# arm-pro-nada.net
KiCad netlist of a schematic drawn in EAGLE
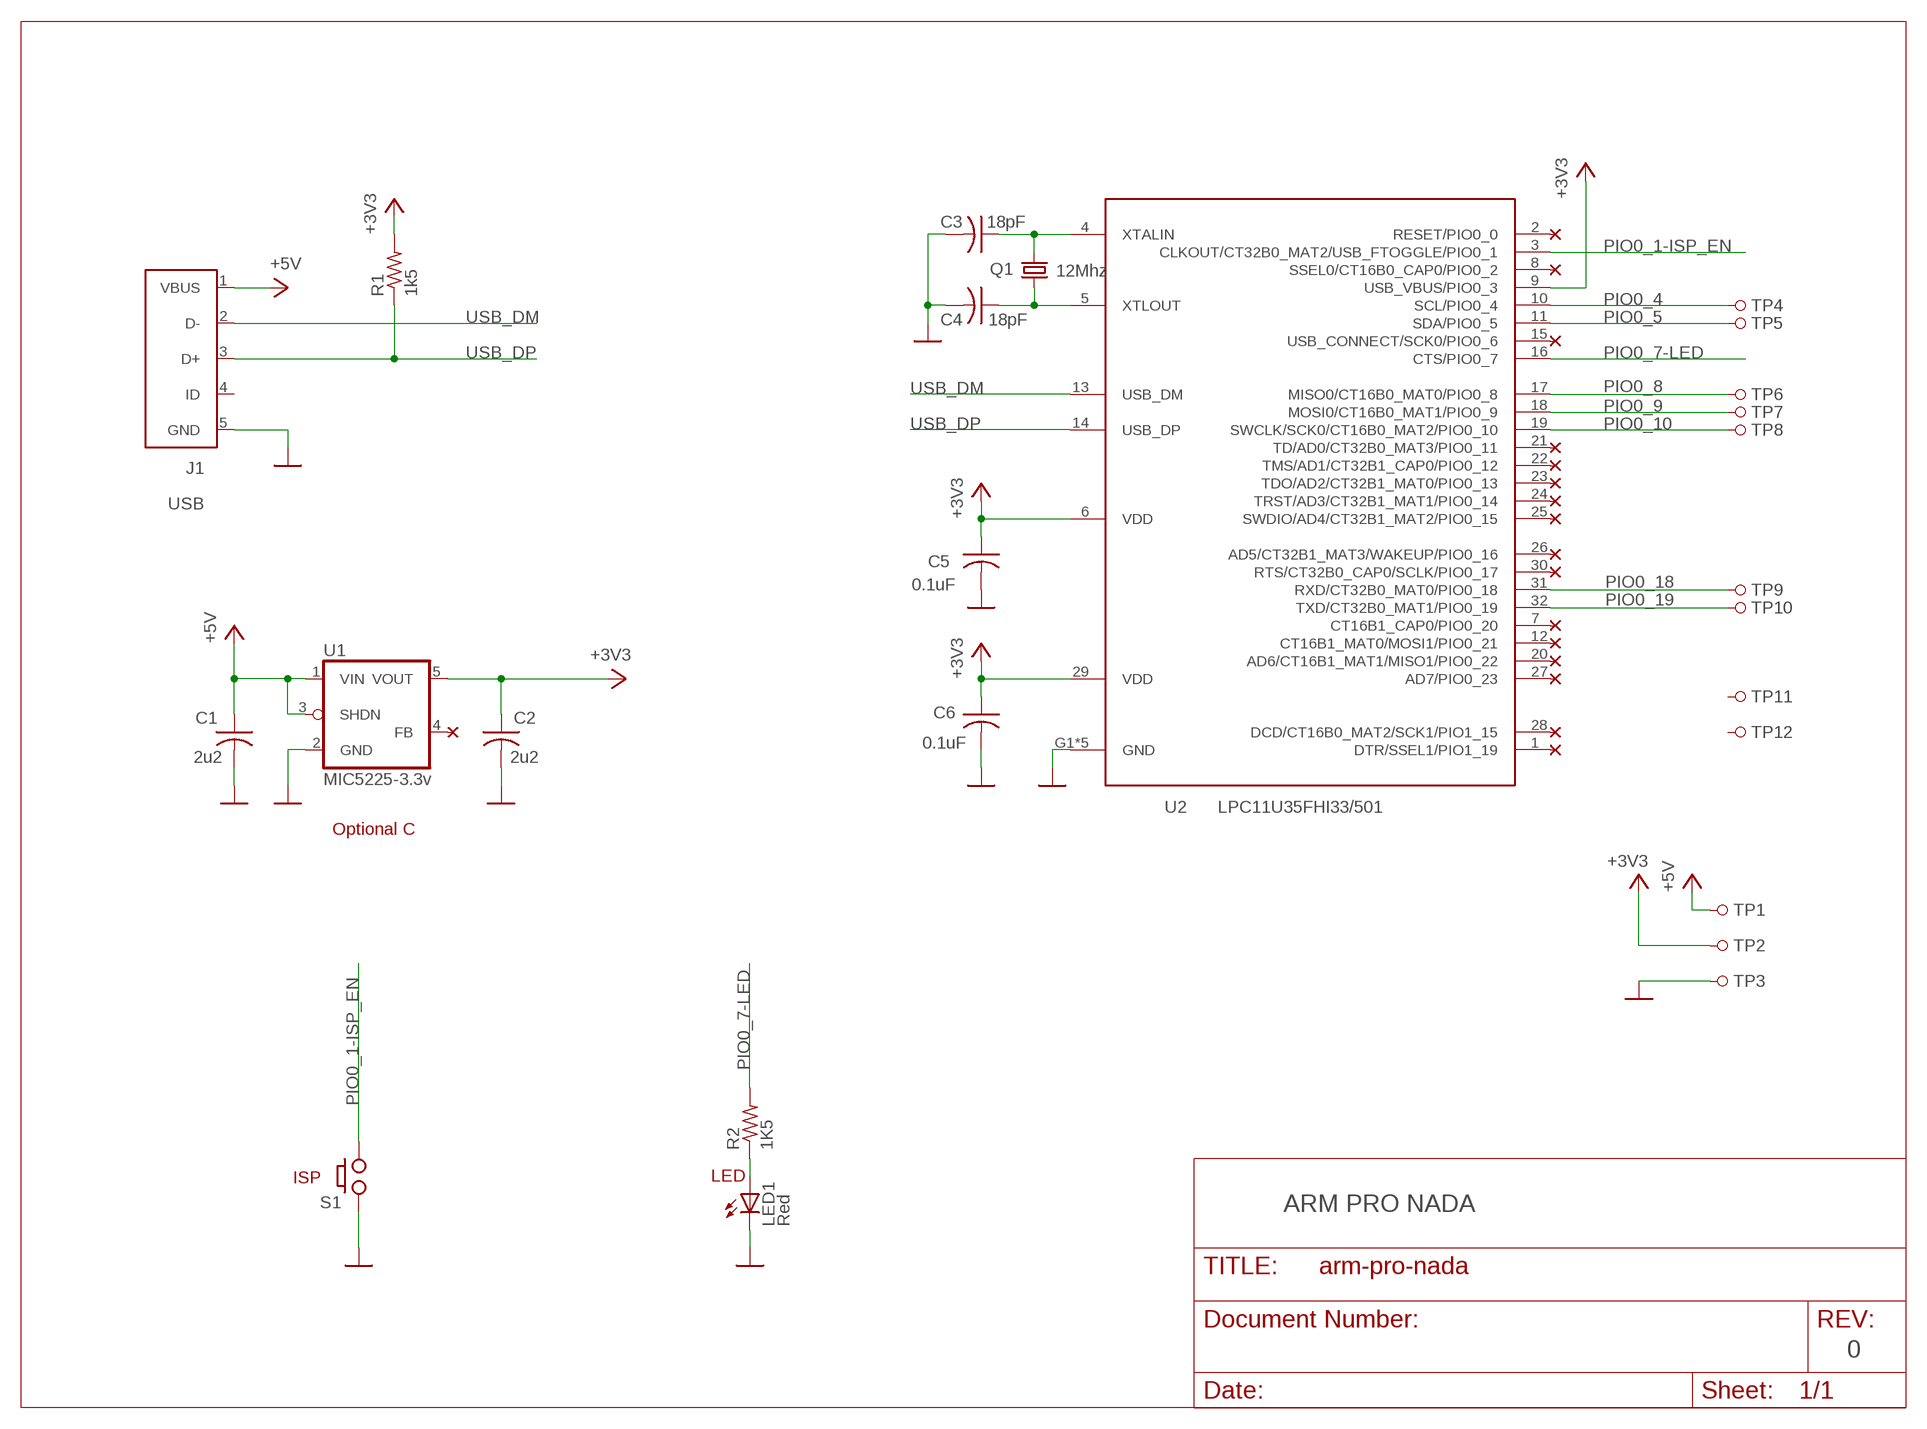
[diagram p0: schematic, sheet 1]

(export (version "E")
  (design (tool "Eeschema 10.0.6"))
  (components
    (comp (ref "C1")
      (value "2u2")
      (footprint "eagle-import:C0402K")
      (libsource (lib "eagle-import") (part "C-USC0402K"))
    )
    (comp (ref "C2")
      (value "2u2")
      (footprint "eagle-import:C0402K")
      (libsource (lib "eagle-import") (part "C-USC0402K"))
    )
    (comp (ref "C3")
      (value "18pF")
      (footprint "eagle-import:C0402K")
      (libsource (lib "eagle-import") (part "C-USC0402K"))
    )
    (comp (ref "C4")
      (value "18pF")
      (footprint "eagle-import:C0402K")
      (libsource (lib "eagle-import") (part "C-USC0402K"))
    )
    (comp (ref "C5")
      (value "0.1uF")
      (footprint "eagle-import:C0402K")
      (libsource (lib "eagle-import") (part "C-USC0402K"))
    )
    (comp (ref "C6")
      (value "0.1uF")
      (footprint "eagle-import:C0402K")
      (libsource (lib "eagle-import") (part "C-USC0402K"))
    )
    (comp (ref "J1")
      (value "USB")
      (footprint "eagle-import:USB-MICRO-ZX62RD-AB-5P8")
      (libsource (lib "eagle-import") (part "USB"))
    )
    (comp (ref "LED1")
      (value "Red")
      (footprint "eagle-import:CHIP-LED0603")
      (libsource (lib "eagle-import") (part "LEDCHIP-LED0603"))
    )
    (comp (ref "Q1")
      (value "12Mhz")
      (footprint "eagle-import:CRYSTAL")
      (libsource (lib "eagle-import") (part "CRYSTALCTS406"))
    )
    (comp (ref "R1")
      (value "1k5")
      (footprint "eagle-import:R0402")
      (libsource (lib "eagle-import") (part "R-US_R0402"))
    )
    (comp (ref "R2")
      (value "1K5")
      (footprint "eagle-import:R0402")
      (libsource (lib "eagle-import") (part "R-US_R0402"))
    )
    (comp (ref "S1")
      (value "PUSH_BUTTON")
      (footprint "eagle-import:PUSH_BUTTON")
      (libsource (lib "eagle-import") (part "PUSH_BUTTON"))
    )
    (comp (ref "TP1")
      (value "HDR1")
      (footprint "eagle-import:1X01")
      (libsource (lib "eagle-import") (part "PINHD-1X1"))
    )
    (comp (ref "TP2")
      (value "HDR1")
      (footprint "eagle-import:1X01")
      (libsource (lib "eagle-import") (part "PINHD-1X1"))
    )
    (comp (ref "TP3")
      (value "HDR1")
      (footprint "eagle-import:1X01")
      (libsource (lib "eagle-import") (part "PINHD-1X1"))
    )
    (comp (ref "TP4")
      (value "HDR1")
      (footprint "eagle-import:1X01")
      (libsource (lib "eagle-import") (part "PINHD-1X1"))
    )
    (comp (ref "TP5")
      (value "HDR1")
      (footprint "eagle-import:1X01")
      (libsource (lib "eagle-import") (part "PINHD-1X1"))
    )
    (comp (ref "TP6")
      (value "HDR1")
      (footprint "eagle-import:1X01")
      (libsource (lib "eagle-import") (part "PINHD-1X1"))
    )
    (comp (ref "TP7")
      (value "HDR1")
      (footprint "eagle-import:1X01")
      (libsource (lib "eagle-import") (part "PINHD-1X1"))
    )
    (comp (ref "TP8")
      (value "HDR1")
      (footprint "eagle-import:1X01")
      (libsource (lib "eagle-import") (part "PINHD-1X1"))
    )
    (comp (ref "TP9")
      (value "HDR1")
      (footprint "eagle-import:1X01")
      (libsource (lib "eagle-import") (part "PINHD-1X1"))
    )
    (comp (ref "TP10")
      (value "HDR1")
      (footprint "eagle-import:1X01")
      (libsource (lib "eagle-import") (part "PINHD-1X1"))
    )
    (comp (ref "TP11")
      (value "HDR1")
      (footprint "eagle-import:1X01")
      (libsource (lib "eagle-import") (part "PINHD-1X1"))
    )
    (comp (ref "TP12")
      (value "HDR1")
      (footprint "eagle-import:1X01")
      (libsource (lib "eagle-import") (part "PINHD-1X1"))
    )
    (comp (ref "U1")
      (value "MIC5225-3.3v")
      (footprint "eagle-import:SOT25")
      (libsource (lib "eagle-import") (part "TC1015"))
    )
    (comp (ref "U2")
      (value "LPC11U35FHI33/501")
      (footprint "eagle-import:HVQFN33-5MM")
      (libsource (lib "eagle-import") (part "LPC11U35FHN33/501"))
    )
  )
  (nets
    (net (code "1") (name "+3V3") (class "Default")
      (node (ref "C2") (pin "1") (pinfunction "1_1") (pintype "passive"))
      (node (ref "C5") (pin "1") (pinfunction "1_1") (pintype "passive"))
      (node (ref "C6") (pin "1") (pinfunction "1_1") (pintype "passive"))
      (node (ref "R1") (pin "2") (pinfunction "2_2") (pintype "passive"))
      (node (ref "TP2") (pin "1") (pinfunction "1_1") (pintype "passive"))
      (node (ref "U1") (pin "5") (pinfunction "VOUT_5") (pintype "power_in"))
      (node (ref "U2") (pin "29") (pinfunction "VDD_29") (pintype "bidirectional"))
      (node (ref "U2") (pin "6") (pinfunction "VDD_6") (pintype "bidirectional"))
      (node (ref "U2") (pin "9") (pinfunction "USB_VBUS/PIO0_3_9") (pintype "bidirectional"))
    )
    (net (code "2") (name "+5V") (class "Default")
      (node (ref "C1") (pin "1") (pinfunction "1_1") (pintype "passive"))
      (node (ref "J1") (pin "1") (pinfunction "VBUS_1") (pintype "bidirectional"))
      (node (ref "TP1") (pin "1") (pinfunction "1_1") (pintype "passive"))
      (node (ref "U1") (pin "1") (pinfunction "VIN_1") (pintype "power_in"))
      (node (ref "U1") (pin "3") (pinfunction "SHDN_3") (pintype "input"))
    )
    (net (code "3") (name "/PIO0_1-ISP_EN") (class "Default")
      (node (ref "S1") (pin "B2") (pinfunction "2_B2") (pintype "passive"))
      (node (ref "U2") (pin "3") (pinfunction "CLKOUT/CT32B0_MAT2/USB_FTOGGLE/PIO0_1_3") (pintype "bidirectional"))
    )
    (net (code "4") (name "/PIO0_4") (class "Default")
      (node (ref "TP4") (pin "1") (pinfunction "1_1") (pintype "passive"))
      (node (ref "U2") (pin "10") (pinfunction "SCL/PIO0_4_10") (pintype "bidirectional"))
    )
    (net (code "5") (name "/PIO0_5") (class "Default")
      (node (ref "TP5") (pin "1") (pinfunction "1_1") (pintype "passive"))
      (node (ref "U2") (pin "11") (pinfunction "SDA/PIO0_5_11") (pintype "bidirectional"))
    )
    (net (code "6") (name "/PIO0_7-LED") (class "Default")
      (node (ref "R2") (pin "2") (pinfunction "2_2") (pintype "passive"))
      (node (ref "U2") (pin "16") (pinfunction "CTS/PIO0_7_16") (pintype "bidirectional"))
    )
    (net (code "7") (name "/PIO0_8") (class "Default")
      (node (ref "TP6") (pin "1") (pinfunction "1_1") (pintype "passive"))
      (node (ref "U2") (pin "17") (pinfunction "MISO0/CT16B0_MAT0/PIO0_8_17") (pintype "bidirectional"))
    )
    (net (code "8") (name "/PIO0_9") (class "Default")
      (node (ref "TP7") (pin "1") (pinfunction "1_1") (pintype "passive"))
      (node (ref "U2") (pin "18") (pinfunction "MOSI0/CT16B0_MAT1/PIO0_9_18") (pintype "bidirectional"))
    )
    (net (code "9") (name "/PIO0_10") (class "Default")
      (node (ref "TP8") (pin "1") (pinfunction "1_1") (pintype "passive"))
      (node (ref "U2") (pin "19") (pinfunction "SWCLK/SCK0/CT16B0_MAT2/PIO0_10_19") (pintype "bidirectional"))
    )
    (net (code "10") (name "/PIO0_18") (class "Default")
      (node (ref "TP9") (pin "1") (pinfunction "1_1") (pintype "passive"))
      (node (ref "U2") (pin "31") (pinfunction "RXD/CT32B0_MAT0/PIO0_18_31") (pintype "bidirectional"))
    )
    (net (code "11") (name "/PIO0_19") (class "Default")
      (node (ref "TP10") (pin "1") (pinfunction "1_1") (pintype "passive"))
      (node (ref "U2") (pin "32") (pinfunction "TXD/CT32B0_MAT1/PIO0_19_32") (pintype "bidirectional"))
    )
    (net (code "12") (name "/USB_DM") (class "Default")
      (node (ref "J1") (pin "2") (pinfunction "D-_2") (pintype "bidirectional"))
      (node (ref "U2") (pin "13") (pinfunction "USB_DM_13") (pintype "bidirectional"))
    )
    (net (code "13") (name "/USB_DP") (class "Default")
      (node (ref "J1") (pin "3") (pinfunction "D+_3") (pintype "bidirectional"))
      (node (ref "R1") (pin "1") (pinfunction "1_1") (pintype "passive"))
      (node (ref "U2") (pin "14") (pinfunction "USB_DP_14") (pintype "bidirectional"))
    )
    (net (code "14") (name "GND") (class "Default")
      (node (ref "C1") (pin "2") (pinfunction "2_2") (pintype "passive"))
      (node (ref "C2") (pin "2") (pinfunction "2_2") (pintype "passive"))
      (node (ref "C3") (pin "2") (pinfunction "2_2") (pintype "passive"))
      (node (ref "C4") (pin "2") (pinfunction "2_2") (pintype "passive"))
      (node (ref "C5") (pin "2") (pinfunction "2_2") (pintype "passive"))
      (node (ref "C6") (pin "2") (pinfunction "2_2") (pintype "passive"))
      (node (ref "J1") (pin "5") (pinfunction "GND_5") (pintype "bidirectional"))
      (node (ref "LED1") (pin "C") (pinfunction "C_C") (pintype "passive"))
      (node (ref "S1") (pin "A1") (pinfunction "1_A1") (pintype "passive"))
      (node (ref "TP3") (pin "1") (pinfunction "1_1") (pintype "passive"))
      (node (ref "U1") (pin "2") (pinfunction "GND_2") (pintype "power_in"))
      (node (ref "U2") (pin "G1") (pinfunction "GND_G1") (pintype "bidirectional"))
      (node (ref "U2") (pin "G2") (pinfunction "GND_G2") (pintype "bidirectional"))
      (node (ref "U2") (pin "G3") (pinfunction "GND_G3") (pintype "bidirectional"))
      (node (ref "U2") (pin "G4") (pinfunction "GND_G4") (pintype "bidirectional"))
      (node (ref "U2") (pin "TAB") (pinfunction "GND_TAB") (pintype "bidirectional"))
    )
    (net (code "15") (name "Net-(LED1-PadA)") (class "Default")
      (node (ref "LED1") (pin "A") (pinfunction "A_A") (pintype "passive"))
      (node (ref "R2") (pin "1") (pinfunction "1_1") (pintype "passive"))
    )
    (net (code "16") (name "Net-(Q1-2)") (class "Default")
      (node (ref "C3") (pin "1") (pinfunction "1_1") (pintype "passive"))
      (node (ref "Q1") (pin "3") (pinfunction "2_3") (pintype "passive"))
      (node (ref "U2") (pin "4") (pinfunction "XTALIN_4") (pintype "bidirectional"))
    )
    (net (code "17") (name "Net-(U2-XTLOUT)") (class "Default")
      (node (ref "C4") (pin "1") (pinfunction "1_1") (pintype "passive"))
      (node (ref "Q1") (pin "1") (pinfunction "1_1") (pintype "passive"))
      (node (ref "U2") (pin "5") (pinfunction "XTLOUT_5") (pintype "bidirectional"))
    )
    (net (code "18") (name "unconnected-(J1-ID-Pad4)") (class "Default")
      (node (ref "J1") (pin "4") (pinfunction "ID_4") (pintype "bidirectional"))
    )
    (net (code "19") (name "unconnected-(TP11-Pad1)") (class "Default")
      (node (ref "TP11") (pin "1") (pinfunction "1_1") (pintype "passive"))
    )
    (net (code "20") (name "unconnected-(TP12-Pad1)") (class "Default")
      (node (ref "TP12") (pin "1") (pinfunction "1_1") (pintype "passive"))
    )
    (net (code "21") (name "unconnected-(U1-FB-Pad4)") (class "Default")
      (node (ref "U1") (pin "4") (pinfunction "FB_4") (pintype "passive"))
    )
    (net (code "22") (name "unconnected-(U2-AD5{slash}CT32B1_MAT3{slash}WAKEUP{slash}PIO0_16-Pad26)") (class "Default")
      (node (ref "U2") (pin "26") (pinfunction "AD5/CT32B1_MAT3/WAKEUP/PIO0_16_26") (pintype "bidirectional"))
    )
    (net (code "23") (name "unconnected-(U2-AD6{slash}CT16B1_MAT1{slash}MISO1{slash}PIO0_22-Pad20)") (class "Default")
      (node (ref "U2") (pin "20") (pinfunction "AD6/CT16B1_MAT1/MISO1/PIO0_22_20") (pintype "bidirectional"))
    )
    (net (code "24") (name "unconnected-(U2-AD7{slash}PIO0_23-Pad27)") (class "Default")
      (node (ref "U2") (pin "27") (pinfunction "AD7/PIO0_23_27") (pintype "bidirectional"))
    )
    (net (code "25") (name "unconnected-(U2-CT16B1_CAP0{slash}PIO0_20-Pad7)") (class "Default")
      (node (ref "U2") (pin "7") (pinfunction "CT16B1_CAP0/PIO0_20_7") (pintype "bidirectional"))
    )
    (net (code "26") (name "unconnected-(U2-CT16B1_MAT0{slash}MOSI1{slash}PIO0_21-Pad12)") (class "Default")
      (node (ref "U2") (pin "12") (pinfunction "CT16B1_MAT0/MOSI1/PIO0_21_12") (pintype "bidirectional"))
    )
    (net (code "27") (name "unconnected-(U2-DCD{slash}CT16B0_MAT2{slash}SCK1{slash}PIO1_15-Pad28)") (class "Default")
      (node (ref "U2") (pin "28") (pinfunction "DCD/CT16B0_MAT2/SCK1/PIO1_15_28") (pintype "bidirectional"))
    )
    (net (code "28") (name "unconnected-(U2-DTR{slash}SSEL1{slash}PIO1_19-Pad1)") (class "Default")
      (node (ref "U2") (pin "1") (pinfunction "DTR/SSEL1/PIO1_19_1") (pintype "bidirectional"))
    )
    (net (code "29") (name "unconnected-(U2-RESET{slash}PIO0_0-Pad2)") (class "Default")
      (node (ref "U2") (pin "2") (pinfunction "RESET/PIO0_0_2") (pintype "bidirectional"))
    )
    (net (code "30") (name "unconnected-(U2-RTS{slash}CT32B0_CAP0{slash}SCLK{slash}PIO0_17-Pad30)") (class "Default")
      (node (ref "U2") (pin "30") (pinfunction "RTS/CT32B0_CAP0/SCLK/PIO0_17_30") (pintype "bidirectional"))
    )
    (net (code "31") (name "unconnected-(U2-SSEL0{slash}CT16B0_CAP0{slash}PIO0_2-Pad8)") (class "Default")
      (node (ref "U2") (pin "8") (pinfunction "SSEL0/CT16B0_CAP0/PIO0_2_8") (pintype "bidirectional"))
    )
    (net (code "32") (name "unconnected-(U2-SWDIO{slash}AD4{slash}CT32B1_MAT2{slash}PIO0_15-Pad25)") (class "Default")
      (node (ref "U2") (pin "25") (pinfunction "SWDIO/AD4/CT32B1_MAT2/PIO0_15_25") (pintype "bidirectional"))
    )
    (net (code "33") (name "unconnected-(U2-TDO{slash}AD2{slash}CT32B1_MAT0{slash}PIO0_13-Pad23)") (class "Default")
      (node (ref "U2") (pin "23") (pinfunction "TDO/AD2/CT32B1_MAT0/PIO0_13_23") (pintype "bidirectional"))
    )
    (net (code "34") (name "unconnected-(U2-TD{slash}AD0{slash}CT32B0_MAT3{slash}PIO0_11-Pad21)") (class "Default")
      (node (ref "U2") (pin "21") (pinfunction "TD/AD0/CT32B0_MAT3/PIO0_11_21") (pintype "bidirectional"))
    )
    (net (code "35") (name "unconnected-(U2-TMS{slash}AD1{slash}CT32B1_CAP0{slash}PIO0_12-Pad22)") (class "Default")
      (node (ref "U2") (pin "22") (pinfunction "TMS/AD1/CT32B1_CAP0/PIO0_12_22") (pintype "bidirectional"))
    )
    (net (code "36") (name "unconnected-(U2-TRST{slash}AD3{slash}CT32B1_MAT1{slash}PIO0_14-Pad24)") (class "Default")
      (node (ref "U2") (pin "24") (pinfunction "TRST/AD3/CT32B1_MAT1/PIO0_14_24") (pintype "bidirectional"))
    )
    (net (code "37") (name "unconnected-(U2-USB_CONNECT{slash}SCK0{slash}PIO0_6-Pad15)") (class "Default")
      (node (ref "U2") (pin "15") (pinfunction "USB_CONNECT/SCK0/PIO0_6_15") (pintype "bidirectional"))
    )
  )
)
